# lego.net
KiCad netlist of a schematic drawn in EAGLE
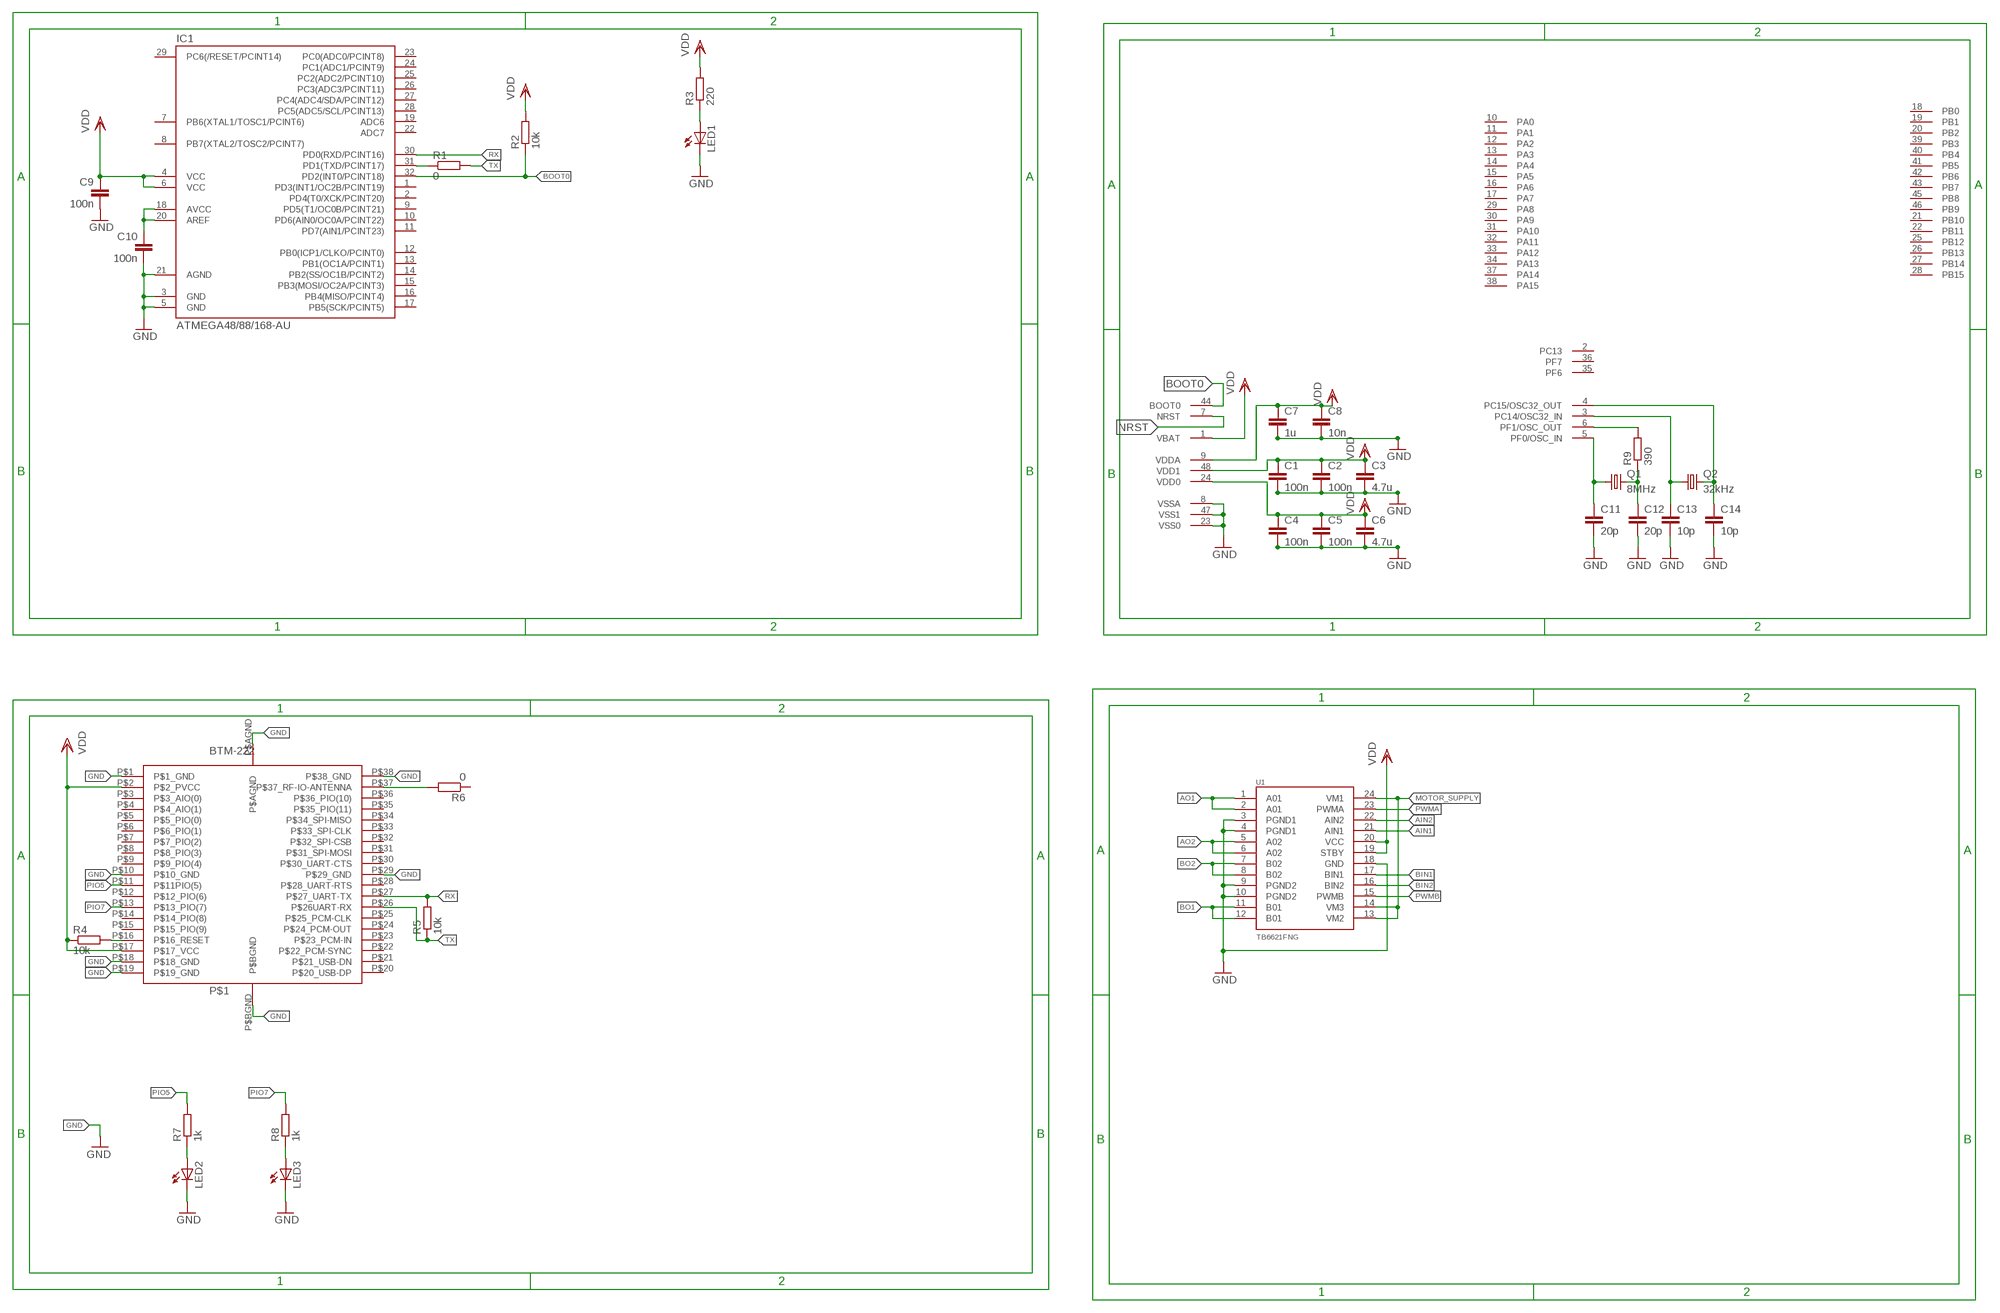
[diagram p0: schematic, sheet 1]

(export (version "E")
  (design (tool "Eeschema 10.0.6"))
  (components
    (comp (ref "C1")
      (value "100n")
      (footprint "eagle-import:C0805")
      (libsource (lib "eagle-import") (part "C-EUC0805"))
    )
    (comp (ref "C2")
      (value "100n")
      (footprint "eagle-import:C0805")
      (libsource (lib "eagle-import") (part "C-EUC0805"))
    )
    (comp (ref "C3")
      (value "4.7u")
      (footprint "eagle-import:C0805")
      (libsource (lib "eagle-import") (part "C-EUC0805"))
    )
    (comp (ref "C4")
      (value "100n")
      (footprint "eagle-import:C0805")
      (libsource (lib "eagle-import") (part "C-EUC0805"))
    )
    (comp (ref "C5")
      (value "100n")
      (footprint "eagle-import:C0805")
      (libsource (lib "eagle-import") (part "C-EUC0805"))
    )
    (comp (ref "C6")
      (value "4.7u")
      (footprint "eagle-import:C0805")
      (libsource (lib "eagle-import") (part "C-EUC0805"))
    )
    (comp (ref "C7")
      (value "1u")
      (footprint "eagle-import:C0805")
      (libsource (lib "eagle-import") (part "C-EUC0805"))
    )
    (comp (ref "C8")
      (value "10n")
      (footprint "eagle-import:C0805")
      (libsource (lib "eagle-import") (part "C-EUC0805"))
    )
    (comp (ref "C9")
      (value "100n")
      (footprint "eagle-import:C0805")
      (libsource (lib "eagle-import") (part "C-EUC0805"))
    )
    (comp (ref "C10")
      (value "100n")
      (footprint "eagle-import:C0805")
      (libsource (lib "eagle-import") (part "C-EUC0805"))
    )
    (comp (ref "C11")
      (value "20p")
      (footprint "eagle-import:C0805")
      (libsource (lib "eagle-import") (part "C-EUC0805"))
    )
    (comp (ref "C12")
      (value "20p")
      (footprint "eagle-import:C0805")
      (libsource (lib "eagle-import") (part "C-EUC0805"))
    )
    (comp (ref "C13")
      (value "10p")
      (footprint "eagle-import:C0805")
      (libsource (lib "eagle-import") (part "C-EUC0805"))
    )
    (comp (ref "C14")
      (value "10p")
      (footprint "eagle-import:C0805")
      (libsource (lib "eagle-import") (part "C-EUC0805"))
    )
    (comp (ref "IC1")
      (value "ATMEGA48/88/168-AU")
      (footprint "eagle-import:TQFP32-08")
      (libsource (lib "eagle-import") (part "ATMEGA48/88/168-AU"))
    )
    (comp (ref "LED1")
      (value "LEDSMT1206")
      (footprint "eagle-import:1206")
      (libsource (lib "eagle-import") (part "LEDSMT1206"))
    )
    (comp (ref "LED2")
      (value "LEDSMT1206")
      (footprint "eagle-import:1206")
      (libsource (lib "eagle-import") (part "LEDSMT1206"))
    )
    (comp (ref "LED3")
      (value "LEDSMT1206")
      (footprint "eagle-import:1206")
      (libsource (lib "eagle-import") (part "LEDSMT1206"))
    )
    (comp (ref "P$1")
      (value "BTM-222")
      (footprint "eagle-import:BTM-222")
      (libsource (lib "eagle-import") (part "BTM-222"))
    )
    (comp (ref "Q1")
      (value "8MHz")
      (footprint "eagle-import:HC49UP")
      (libsource (lib "eagle-import") (part "CRYSTALHC49UP"))
    )
    (comp (ref "Q2")
      (value "32kHz")
      (footprint "eagle-import:HC49UP")
      (libsource (lib "eagle-import") (part "CRYSTALHC49UP"))
    )
    (comp (ref "R1")
      (value "0")
      (footprint "eagle-import:R0805")
      (libsource (lib "eagle-import") (part "R-EU_R0805"))
    )
    (comp (ref "R2")
      (value "10k")
      (footprint "eagle-import:R0805")
      (libsource (lib "eagle-import") (part "R-EU_R0805"))
    )
    (comp (ref "R3")
      (value "220")
      (footprint "eagle-import:R0805")
      (libsource (lib "eagle-import") (part "R-EU_R0805"))
    )
    (comp (ref "R4")
      (value "10k")
      (footprint "eagle-import:R0805")
      (libsource (lib "eagle-import") (part "R-EU_R0805"))
    )
    (comp (ref "R5")
      (value "10k")
      (footprint "eagle-import:R0805")
      (libsource (lib "eagle-import") (part "R-EU_R0805"))
    )
    (comp (ref "R6")
      (value "0")
      (footprint "eagle-import:R0805")
      (libsource (lib "eagle-import") (part "R-EU_R0805"))
    )
    (comp (ref "R7")
      (value "1k")
      (footprint "eagle-import:R0805")
      (libsource (lib "eagle-import") (part "R-EU_R0805"))
    )
    (comp (ref "R8")
      (value "1k")
      (footprint "eagle-import:R0805")
      (libsource (lib "eagle-import") (part "R-EU_R0805"))
    )
    (comp (ref "R9")
      (value "390")
      (footprint "eagle-import:R0805")
      (libsource (lib "eagle-import") (part "R-EU_R0805"))
    )
    (comp (ref "U$1")
      (value "STM32F050")
      (footprint "eagle-import:LQFP48")
      (libsource (lib "eagle-import") (part "STM32F050"))
    )
    (comp (ref "U1")
      (value "TB6621FNG")
      (footprint "eagle-import:SSOP24")
      (libsource (lib "eagle-import") (part "TB6621FNG"))
    )
  )
  (nets
    (net (code "1") (name "AIN1") (class "Default")
      (node (ref "U1") (pin "21") (pinfunction "AIN1_21") (pintype "bidirectional"))
    )
    (net (code "2") (name "AIN2") (class "Default")
      (node (ref "U1") (pin "22") (pinfunction "AIN2_22") (pintype "bidirectional"))
    )
    (net (code "3") (name "AO1") (class "Default")
      (node (ref "U1") (pin "1") (pinfunction "A01_1") (pintype "bidirectional"))
      (node (ref "U1") (pin "2") (pinfunction "A01_2") (pintype "bidirectional"))
    )
    (net (code "4") (name "AO2") (class "Default")
      (node (ref "U1") (pin "5") (pinfunction "A02_5") (pintype "bidirectional"))
      (node (ref "U1") (pin "6") (pinfunction "A02_6") (pintype "bidirectional"))
    )
    (net (code "5") (name "BIN1") (class "Default")
      (node (ref "U1") (pin "17") (pinfunction "BIN1_17") (pintype "bidirectional"))
    )
    (net (code "6") (name "BIN2") (class "Default")
      (node (ref "U1") (pin "16") (pinfunction "BIN2_16") (pintype "bidirectional"))
    )
    (net (code "7") (name "BO1") (class "Default")
      (node (ref "U1") (pin "11") (pinfunction "B01_11") (pintype "bidirectional"))
      (node (ref "U1") (pin "12") (pinfunction "B01_12") (pintype "bidirectional"))
    )
    (net (code "8") (name "BO2") (class "Default")
      (node (ref "U1") (pin "7") (pinfunction "B02_7") (pintype "bidirectional"))
      (node (ref "U1") (pin "8") (pinfunction "B02_8") (pintype "bidirectional"))
    )
    (net (code "9") (name "BOOT0") (class "Default")
      (node (ref "IC1") (pin "32") (pinfunction "PD2(INT0/PCINT18)_32") (pintype "bidirectional"))
      (node (ref "R2") (pin "1") (pinfunction "1_1") (pintype "passive"))
      (node (ref "U$1") (pin "44") (pinfunction "BOOT0_44") (pintype "input"))
    )
    (net (code "10") (name "GND") (class "Default")
      (node (ref "C1") (pin "2") (pinfunction "2_2") (pintype "passive"))
      (node (ref "C10") (pin "2") (pinfunction "2_2") (pintype "passive"))
      (node (ref "C11") (pin "2") (pinfunction "2_2") (pintype "passive"))
      (node (ref "C12") (pin "2") (pinfunction "2_2") (pintype "passive"))
      (node (ref "C13") (pin "2") (pinfunction "2_2") (pintype "passive"))
      (node (ref "C14") (pin "2") (pinfunction "2_2") (pintype "passive"))
      (node (ref "C2") (pin "2") (pinfunction "2_2") (pintype "passive"))
      (node (ref "C3") (pin "2") (pinfunction "2_2") (pintype "passive"))
      (node (ref "C4") (pin "2") (pinfunction "2_2") (pintype "passive"))
      (node (ref "C5") (pin "2") (pinfunction "2_2") (pintype "passive"))
      (node (ref "C6") (pin "2") (pinfunction "2_2") (pintype "passive"))
      (node (ref "C7") (pin "2") (pinfunction "2_2") (pintype "passive"))
      (node (ref "C8") (pin "2") (pinfunction "2_2") (pintype "passive"))
      (node (ref "C9") (pin "2") (pinfunction "2_2") (pintype "passive"))
      (node (ref "IC1") (pin "21") (pinfunction "AGND_21") (pintype "power_in"))
      (node (ref "IC1") (pin "3") (pinfunction "GND_3") (pintype "power_in"))
      (node (ref "IC1") (pin "5") (pinfunction "GND_5") (pintype "power_in"))
      (node (ref "LED1") (pin "C") (pinfunction "C_C") (pintype "passive"))
      (node (ref "LED2") (pin "C") (pinfunction "C_C") (pintype "passive"))
      (node (ref "LED3") (pin "C") (pinfunction "C_C") (pintype "passive"))
      (node (ref "P$1") (pin "P$1") (pinfunction "P$1_GND_P$1") (pintype "power_in"))
      (node (ref "P$1") (pin "P$10") (pinfunction "P$10_GND_P$10") (pintype "power_in"))
      (node (ref "P$1") (pin "P$18") (pinfunction "P$18_GND_P$18") (pintype "power_in"))
      (node (ref "P$1") (pin "P$19") (pinfunction "P$19_GND_P$19") (pintype "power_in"))
      (node (ref "P$1") (pin "P$29") (pinfunction "P$29_GND_P$29") (pintype "power_in"))
      (node (ref "P$1") (pin "P$38") (pinfunction "P$38_GND_P$38") (pintype "power_in"))
      (node (ref "P$1") (pin "P$AGND") (pinfunction "P$AGND_P$AGND") (pintype "power_in"))
      (node (ref "P$1") (pin "P$BGND") (pinfunction "P$BGND_P$BGND") (pintype "power_in"))
      (node (ref "U$1") (pin "23") (pinfunction "VSS0_23") (pintype "power_in"))
      (node (ref "U$1") (pin "47") (pinfunction "VSS1_47") (pintype "power_in"))
      (node (ref "U$1") (pin "8") (pinfunction "VSSA_8") (pintype "power_in"))
      (node (ref "U1") (pin "10") (pinfunction "PGND2_10") (pintype "bidirectional"))
      (node (ref "U1") (pin "18") (pinfunction "GND_18") (pintype "bidirectional"))
      (node (ref "U1") (pin "3") (pinfunction "PGND1_3") (pintype "bidirectional"))
      (node (ref "U1") (pin "4") (pinfunction "PGND1_4") (pintype "bidirectional"))
      (node (ref "U1") (pin "9") (pinfunction "PGND2_9") (pintype "bidirectional"))
    )
    (net (code "11") (name "MOTOR_SUPPLY") (class "Default")
      (node (ref "U1") (pin "13") (pinfunction "VM2_13") (pintype "bidirectional"))
      (node (ref "U1") (pin "14") (pinfunction "VM3_14") (pintype "bidirectional"))
      (node (ref "U1") (pin "24") (pinfunction "VM1_24") (pintype "bidirectional"))
    )
    (net (code "12") (name "NRST") (class "Default")
      (node (ref "U$1") (pin "7") (pinfunction "NRST_7") (pintype "input"))
    )
    (net (code "13") (name "Net-(C12-Pad1)") (class "Default")
      (node (ref "C12") (pin "1") (pinfunction "1_1") (pintype "passive"))
      (node (ref "Q1") (pin "2") (pinfunction "2_2") (pintype "passive"))
      (node (ref "R9") (pin "1") (pinfunction "1_1") (pintype "passive"))
    )
    (net (code "14") (name "Net-(IC1-AREF)") (class "Default")
      (node (ref "C10") (pin "1") (pinfunction "1_1") (pintype "passive"))
      (node (ref "IC1") (pin "18") (pinfunction "AVCC_18") (pintype "passive"))
      (node (ref "IC1") (pin "20") (pinfunction "AREF_20") (pintype "passive"))
    )
    (net (code "15") (name "Net-(IC1-PD1(TXD{slash}PCINT17))") (class "Default")
      (node (ref "IC1") (pin "31") (pinfunction "PD1(TXD/PCINT17)_31") (pintype "bidirectional"))
      (node (ref "R1") (pin "1") (pinfunction "1_1") (pintype "passive"))
    )
    (net (code "16") (name "Net-(LED1-PadA)") (class "Default")
      (node (ref "LED1") (pin "A") (pinfunction "A_A") (pintype "passive"))
      (node (ref "R3") (pin "1") (pinfunction "1_1") (pintype "passive"))
    )
    (net (code "17") (name "Net-(LED2-PadA)") (class "Default")
      (node (ref "LED2") (pin "A") (pinfunction "A_A") (pintype "passive"))
      (node (ref "R7") (pin "1") (pinfunction "1_1") (pintype "passive"))
    )
    (net (code "18") (name "Net-(LED3-PadA)") (class "Default")
      (node (ref "LED3") (pin "A") (pinfunction "A_A") (pintype "passive"))
      (node (ref "R8") (pin "1") (pinfunction "1_1") (pintype "passive"))
    )
    (net (code "19") (name "Net-(P$1-P$16_RESET)") (class "Default")
      (node (ref "P$1") (pin "P$16") (pinfunction "P$16_RESET_P$16") (pintype "input"))
      (node (ref "R4") (pin "2") (pinfunction "2_2") (pintype "passive"))
    )
    (net (code "20") (name "Net-(P$1-P$37_RF-IO-ANTENNA)") (class "Default")
      (node (ref "P$1") (pin "P$37") (pinfunction "P$37_RF-IO-ANTENNA_P$37") (pintype "bidirectional"))
      (node (ref "R6") (pin "2") (pinfunction "2_2") (pintype "passive"))
    )
    (net (code "21") (name "Net-(U$1D-PC14{slash}OSC32_IN)") (class "Default")
      (node (ref "C13") (pin "1") (pinfunction "1_1") (pintype "passive"))
      (node (ref "Q2") (pin "1") (pinfunction "1_1") (pintype "passive"))
      (node (ref "U$1") (pin "3") (pinfunction "PC14/OSC32_IN_3") (pintype "open_collector"))
    )
    (net (code "22") (name "Net-(U$1D-PC15{slash}OSC32_OUT)") (class "Default")
      (node (ref "C14") (pin "1") (pinfunction "1_1") (pintype "passive"))
      (node (ref "Q2") (pin "2") (pinfunction "2_2") (pintype "passive"))
      (node (ref "U$1") (pin "4") (pinfunction "PC15/OSC32_OUT_4") (pintype "open_collector"))
    )
    (net (code "23") (name "Net-(U$1D-PF0{slash}OSC_IN)") (class "Default")
      (node (ref "C11") (pin "1") (pinfunction "1_1") (pintype "passive"))
      (node (ref "Q1") (pin "1") (pinfunction "1_1") (pintype "passive"))
      (node (ref "U$1") (pin "5") (pinfunction "PF0/OSC_IN_5") (pintype "open_collector"))
    )
    (net (code "24") (name "Net-(U$1D-PF1{slash}OSC_OUT)") (class "Default")
      (node (ref "R9") (pin "2") (pinfunction "2_2") (pintype "passive"))
      (node (ref "U$1") (pin "6") (pinfunction "PF1/OSC_OUT_6") (pintype "open_collector"))
    )
    (net (code "25") (name "PIO5") (class "Default")
      (node (ref "P$1") (pin "P$11") (pinfunction "P$11PIO(5)_P$11") (pintype "bidirectional"))
      (node (ref "R7") (pin "2") (pinfunction "2_2") (pintype "passive"))
    )
    (net (code "26") (name "PIO7") (class "Default")
      (node (ref "P$1") (pin "P$13") (pinfunction "P$13_PIO(7)_P$13") (pintype "bidirectional"))
      (node (ref "R8") (pin "2") (pinfunction "2_2") (pintype "passive"))
    )
    (net (code "27") (name "PWMA") (class "Default")
      (node (ref "U1") (pin "23") (pinfunction "PWMA_23") (pintype "bidirectional"))
    )
    (net (code "28") (name "PWMB") (class "Default")
      (node (ref "U1") (pin "15") (pinfunction "PWMB_15") (pintype "bidirectional"))
    )
    (net (code "29") (name "RX") (class "Default")
      (node (ref "IC1") (pin "30") (pinfunction "PD0(RXD/PCINT16)_30") (pintype "bidirectional"))
      (node (ref "P$1") (pin "P$27") (pinfunction "P$27_UART-TX_P$27") (pintype "output"))
      (node (ref "R5") (pin "2") (pinfunction "2_2") (pintype "passive"))
    )
    (net (code "30") (name "TX") (class "Default")
      (node (ref "P$1") (pin "P$26") (pinfunction "P$26UART-RX_P$26") (pintype "input"))
      (node (ref "R1") (pin "2") (pinfunction "2_2") (pintype "passive"))
      (node (ref "R5") (pin "1") (pinfunction "1_1") (pintype "passive"))
    )
    (net (code "31") (name "VDD") (class "Default")
      (node (ref "C1") (pin "1") (pinfunction "1_1") (pintype "passive"))
      (node (ref "C2") (pin "1") (pinfunction "1_1") (pintype "passive"))
      (node (ref "C3") (pin "1") (pinfunction "1_1") (pintype "passive"))
      (node (ref "C4") (pin "1") (pinfunction "1_1") (pintype "passive"))
      (node (ref "C5") (pin "1") (pinfunction "1_1") (pintype "passive"))
      (node (ref "C6") (pin "1") (pinfunction "1_1") (pintype "passive"))
      (node (ref "C7") (pin "1") (pinfunction "1_1") (pintype "passive"))
      (node (ref "C8") (pin "1") (pinfunction "1_1") (pintype "passive"))
      (node (ref "C9") (pin "1") (pinfunction "1_1") (pintype "passive"))
      (node (ref "IC1") (pin "4") (pinfunction "VCC_4") (pintype "power_in"))
      (node (ref "IC1") (pin "6") (pinfunction "VCC_6") (pintype "power_in"))
      (node (ref "P$1") (pin "P$17") (pinfunction "P$17_VCC_P$17") (pintype "power_in"))
      (node (ref "P$1") (pin "P$2") (pinfunction "P$2_PVCC_P$2") (pintype "power_in"))
      (node (ref "R2") (pin "2") (pinfunction "2_2") (pintype "passive"))
      (node (ref "R3") (pin "2") (pinfunction "2_2") (pintype "passive"))
      (node (ref "R4") (pin "1") (pinfunction "1_1") (pintype "passive"))
      (node (ref "U$1") (pin "1") (pinfunction "VBAT_1") (pintype "power_in"))
      (node (ref "U$1") (pin "24") (pinfunction "VDD0_24") (pintype "power_in"))
      (node (ref "U$1") (pin "48") (pinfunction "VDD1_48") (pintype "power_in"))
      (node (ref "U$1") (pin "9") (pinfunction "VDDA_9") (pintype "power_in"))
      (node (ref "U1") (pin "19") (pinfunction "STBY_19") (pintype "bidirectional"))
      (node (ref "U1") (pin "20") (pinfunction "VCC_20") (pintype "bidirectional"))
    )
    (net (code "32") (name "unconnected-(IC1-ADC6-Pad19)") (class "Default")
      (node (ref "IC1") (pin "19") (pinfunction "ADC6_19") (pintype "passive"))
    )
    (net (code "33") (name "unconnected-(IC1-ADC7-Pad22)") (class "Default")
      (node (ref "IC1") (pin "22") (pinfunction "ADC7_22") (pintype "passive"))
    )
    (net (code "34") (name "unconnected-(IC1-PB0(ICP1{slash}CLKO{slash}PCINT0)-Pad12)") (class "Default")
      (node (ref "IC1") (pin "12") (pinfunction "PB0(ICP1/CLKO/PCINT0)_12") (pintype "bidirectional"))
    )
    (net (code "35") (name "unconnected-(IC1-PB1(OC1A{slash}PCINT1)-Pad13)") (class "Default")
      (node (ref "IC1") (pin "13") (pinfunction "PB1(OC1A/PCINT1)_13") (pintype "bidirectional"))
    )
    (net (code "36") (name "unconnected-(IC1-PB2(SS{slash}OC1B{slash}PCINT2)-Pad14)") (class "Default")
      (node (ref "IC1") (pin "14") (pinfunction "PB2(SS/OC1B/PCINT2)_14") (pintype "bidirectional"))
    )
    (net (code "37") (name "unconnected-(IC1-PB3(MOSI{slash}OC2A{slash}PCINT3)-Pad15)") (class "Default")
      (node (ref "IC1") (pin "15") (pinfunction "PB3(MOSI/OC2A/PCINT3)_15") (pintype "bidirectional"))
    )
    (net (code "38") (name "unconnected-(IC1-PB4(MISO{slash}PCINT4)-Pad16)") (class "Default")
      (node (ref "IC1") (pin "16") (pinfunction "PB4(MISO/PCINT4)_16") (pintype "bidirectional"))
    )
    (net (code "39") (name "unconnected-(IC1-PB5(SCK{slash}PCINT5)-Pad17)") (class "Default")
      (node (ref "IC1") (pin "17") (pinfunction "PB5(SCK/PCINT5)_17") (pintype "bidirectional"))
    )
    (net (code "40") (name "unconnected-(IC1-PB6(XTAL1{slash}TOSC1{slash}PCINT6)-Pad7)") (class "Default")
      (node (ref "IC1") (pin "7") (pinfunction "PB6(XTAL1/TOSC1/PCINT6)_7") (pintype "bidirectional"))
    )
    (net (code "41") (name "unconnected-(IC1-PB7(XTAL2{slash}TOSC2{slash}PCINT7)-Pad8)") (class "Default")
      (node (ref "IC1") (pin "8") (pinfunction "PB7(XTAL2/TOSC2/PCINT7)_8") (pintype "bidirectional"))
    )
    (net (code "42") (name "unconnected-(IC1-PC0(ADC0{slash}PCINT8)-Pad23)") (class "Default")
      (node (ref "IC1") (pin "23") (pinfunction "PC0(ADC0/PCINT8)_23") (pintype "bidirectional"))
    )
    (net (code "43") (name "unconnected-(IC1-PC1(ADC1{slash}PCINT9)-Pad24)") (class "Default")
      (node (ref "IC1") (pin "24") (pinfunction "PC1(ADC1/PCINT9)_24") (pintype "bidirectional"))
    )
    (net (code "44") (name "unconnected-(IC1-PC2(ADC2{slash}PCINT10)-Pad25)") (class "Default")
      (node (ref "IC1") (pin "25") (pinfunction "PC2(ADC2/PCINT10)_25") (pintype "bidirectional"))
    )
    (net (code "45") (name "unconnected-(IC1-PC3(ADC3{slash}PCINT11)-Pad26)") (class "Default")
      (node (ref "IC1") (pin "26") (pinfunction "PC3(ADC3/PCINT11)_26") (pintype "bidirectional"))
    )
    (net (code "46") (name "unconnected-(IC1-PC4(ADC4{slash}SDA{slash}PCINT12)-Pad27)") (class "Default")
      (node (ref "IC1") (pin "27") (pinfunction "PC4(ADC4/SDA/PCINT12)_27") (pintype "bidirectional"))
    )
    (net (code "47") (name "unconnected-(IC1-PC5(ADC5{slash}SCL{slash}PCINT13)-Pad28)") (class "Default")
      (node (ref "IC1") (pin "28") (pinfunction "PC5(ADC5/SCL/PCINT13)_28") (pintype "bidirectional"))
    )
    (net (code "48") (name "unconnected-(IC1-PC6({slash}RESET{slash}PCINT14)-Pad29)") (class "Default")
      (node (ref "IC1") (pin "29") (pinfunction "PC6(/RESET/PCINT14)_29") (pintype "bidirectional"))
    )
    (net (code "49") (name "unconnected-(IC1-PD3(INT1{slash}OC2B{slash}PCINT19)-Pad1)") (class "Default")
      (node (ref "IC1") (pin "1") (pinfunction "PD3(INT1/OC2B/PCINT19)_1") (pintype "bidirectional"))
    )
    (net (code "50") (name "unconnected-(IC1-PD4(T0{slash}XCK{slash}PCINT20)-Pad2)") (class "Default")
      (node (ref "IC1") (pin "2") (pinfunction "PD4(T0/XCK/PCINT20)_2") (pintype "bidirectional"))
    )
    (net (code "51") (name "unconnected-(IC1-PD5(T1{slash}OC0B{slash}PCINT21)-Pad9)") (class "Default")
      (node (ref "IC1") (pin "9") (pinfunction "PD5(T1/OC0B/PCINT21)_9") (pintype "bidirectional"))
    )
    (net (code "52") (name "unconnected-(IC1-PD6(AIN0{slash}OC0A{slash}PCINT22)-Pad10)") (class "Default")
      (node (ref "IC1") (pin "10") (pinfunction "PD6(AIN0/OC0A/PCINT22)_10") (pintype "bidirectional"))
    )
    (net (code "53") (name "unconnected-(IC1-PD7(AIN1{slash}PCINT23)-Pad11)") (class "Default")
      (node (ref "IC1") (pin "11") (pinfunction "PD7(AIN1/PCINT23)_11") (pintype "bidirectional"))
    )
    (net (code "54") (name "unconnected-(P$1-P$3_AIO(0)-PadP$3)") (class "Default")
      (node (ref "P$1") (pin "P$3") (pinfunction "P$3_AIO(0)_P$3") (pintype "bidirectional"))
    )
    (net (code "55") (name "unconnected-(P$1-P$4_AIO(1)-PadP$4)") (class "Default")
      (node (ref "P$1") (pin "P$4") (pinfunction "P$4_AIO(1)_P$4") (pintype "bidirectional"))
    )
    (net (code "56") (name "unconnected-(P$1-P$5_PIO(0)-PadP$5)") (class "Default")
      (node (ref "P$1") (pin "P$5") (pinfunction "P$5_PIO(0)_P$5") (pintype "bidirectional"))
    )
    (net (code "57") (name "unconnected-(P$1-P$6_PIO(1)-PadP$6)") (class "Default")
      (node (ref "P$1") (pin "P$6") (pinfunction "P$6_PIO(1)_P$6") (pintype "bidirectional"))
    )
    (net (code "58") (name "unconnected-(P$1-P$7_PIO(2)-PadP$7)") (class "Default")
      (node (ref "P$1") (pin "P$7") (pinfunction "P$7_PIO(2)_P$7") (pintype "bidirectional"))
    )
    (net (code "59") (name "unconnected-(P$1-P$8_PIO(3)-PadP$8)") (class "Default")
      (node (ref "P$1") (pin "P$8") (pinfunction "P$8_PIO(3)_P$8") (pintype "bidirectional"))
    )
    (net (code "60") (name "unconnected-(P$1-P$9_PIO(4)-PadP$9)") (class "Default")
      (node (ref "P$1") (pin "P$9") (pinfunction "P$9_PIO(4)_P$9") (pintype "bidirectional"))
    )
    (net (code "61") (name "unconnected-(P$1-P$12_PIO(6)-PadP$12)") (class "Default")
      (node (ref "P$1") (pin "P$12") (pinfunction "P$12_PIO(6)_P$12") (pintype "bidirectional"))
    )
    (net (code "62") (name "unconnected-(P$1-P$14_PIO(8)-PadP$14)") (class "Default")
      (node (ref "P$1") (pin "P$14") (pinfunction "P$14_PIO(8)_P$14") (pintype "bidirectional"))
    )
    (net (code "63") (name "unconnected-(P$1-P$15_PIO(9)-PadP$15)") (class "Default")
      (node (ref "P$1") (pin "P$15") (pinfunction "P$15_PIO(9)_P$15") (pintype "bidirectional"))
    )
    (net (code "64") (name "unconnected-(P$1-P$20_USB-DP-PadP$20)") (class "Default")
      (node (ref "P$1") (pin "P$20") (pinfunction "P$20_USB-DP_P$20") (pintype "bidirectional"))
    )
    (net (code "65") (name "unconnected-(P$1-P$21_USB-DN-PadP$21)") (class "Default")
      (node (ref "P$1") (pin "P$21") (pinfunction "P$21_USB-DN_P$21") (pintype "bidirectional"))
    )
    (net (code "66") (name "unconnected-(P$1-P$22_PCM-SYNC-PadP$22)") (class "Default")
      (node (ref "P$1") (pin "P$22") (pinfunction "P$22_PCM-SYNC_P$22") (pintype "bidirectional"))
    )
    (net (code "67") (name "unconnected-(P$1-P$23_PCM-IN-PadP$23)") (class "Default")
      (node (ref "P$1") (pin "P$23") (pinfunction "P$23_PCM-IN_P$23") (pintype "input"))
    )
    (net (code "68") (name "unconnected-(P$1-P$24_PCM-OUT-PadP$24)") (class "Default")
      (node (ref "P$1") (pin "P$24") (pinfunction "P$24_PCM-OUT_P$24") (pintype "output"))
    )
    (net (code "69") (name "unconnected-(P$1-P$25_PCM-CLK-PadP$25)") (class "Default")
      (node (ref "P$1") (pin "P$25") (pinfunction "P$25_PCM-CLK_P$25") (pintype "bidirectional"))
    )
    (net (code "70") (name "unconnected-(P$1-P$28_UART-RTS-PadP$28)") (class "Default")
      (node (ref "P$1") (pin "P$28") (pinfunction "P$28_UART-RTS_P$28") (pintype "output"))
    )
    (net (code "71") (name "unconnected-(P$1-P$30_UART-CTS-PadP$30)") (class "Default")
      (node (ref "P$1") (pin "P$30") (pinfunction "P$30_UART-CTS_P$30") (pintype "input"))
    )
    (net (code "72") (name "unconnected-(P$1-P$31_SPI-MOSI-PadP$31)") (class "Default")
      (node (ref "P$1") (pin "P$31") (pinfunction "P$31_SPI-MOSI_P$31") (pintype "input"))
    )
    (net (code "73") (name "unconnected-(P$1-P$32_SPI-CSB-PadP$32)") (class "Default")
      (node (ref "P$1") (pin "P$32") (pinfunction "P$32_SPI-CSB_P$32") (pintype "input"))
    )
    (net (code "74") (name "unconnected-(P$1-P$33_SPI-CLK-PadP$33)") (class "Default")
      (node (ref "P$1") (pin "P$33") (pinfunction "P$33_SPI-CLK_P$33") (pintype "input"))
    )
    (net (code "75") (name "unconnected-(P$1-P$34_SPI-MISO-PadP$34)") (class "Default")
      (node (ref "P$1") (pin "P$34") (pinfunction "P$34_SPI-MISO_P$34") (pintype "output"))
    )
    (net (code "76") (name "unconnected-(P$1-P$35_PIO(11)-PadP$35)") (class "Default")
      (node (ref "P$1") (pin "P$35") (pinfunction "P$35_PIO(11)_P$35") (pintype "bidirectional"))
    )
    (net (code "77") (name "unconnected-(P$1-P$36_PIO(10)-PadP$36)") (class "Default")
      (node (ref "P$1") (pin "P$36") (pinfunction "P$36_PIO(10)_P$36") (pintype "bidirectional"))
    )
    (net (code "78") (name "unconnected-(R6-Pad1)") (class "Default")
      (node (ref "R6") (pin "1") (pinfunction "1_1") (pintype "passive"))
    )
    (net (code "79") (name "unconnected-(U$1A-PA0-Pad10)") (class "Default")
      (node (ref "U$1") (pin "10") (pinfunction "PA0_10") (pintype "open_collector"))
    )
    (net (code "80") (name "unconnected-(U$1A-PA1-Pad11)") (class "Default")
      (node (ref "U$1") (pin "11") (pinfunction "PA1_11") (pintype "open_collector"))
    )
    (net (code "81") (name "unconnected-(U$1A-PA2-Pad12)") (class "Default")
      (node (ref "U$1") (pin "12") (pinfunction "PA2_12") (pintype "open_collector"))
    )
    (net (code "82") (name "unconnected-(U$1A-PA3-Pad13)") (class "Default")
      (node (ref "U$1") (pin "13") (pinfunction "PA3_13") (pintype "open_collector"))
    )
    (net (code "83") (name "unconnected-(U$1A-PA4-Pad14)") (class "Default")
      (node (ref "U$1") (pin "14") (pinfunction "PA4_14") (pintype "open_collector"))
    )
    (net (code "84") (name "unconnected-(U$1A-PA5-Pad15)") (class "Default")
      (node (ref "U$1") (pin "15") (pinfunction "PA5_15") (pintype "open_collector"))
    )
    (net (code "85") (name "unconnected-(U$1A-PA6-Pad16)") (class "Default")
      (node (ref "U$1") (pin "16") (pinfunction "PA6_16") (pintype "open_collector"))
    )
    (net (code "86") (name "unconnected-(U$1A-PA7-Pad17)") (class "Default")
      (node (ref "U$1") (pin "17") (pinfunction "PA7_17") (pintype "open_collector"))
    )
    (net (code "87") (name "unconnected-(U$1A-PA8-Pad29)") (class "Default")
      (node (ref "U$1") (pin "29") (pinfunction "PA8_29") (pintype "open_collector"))
    )
    (net (code "88") (name "unconnected-(U$1A-PA9-Pad30)") (class "Default")
      (node (ref "U$1") (pin "30") (pinfunction "PA9_30") (pintype "open_collector"))
    )
    (net (code "89") (name "unconnected-(U$1A-PA10-Pad31)") (class "Default")
      (node (ref "U$1") (pin "31") (pinfunction "PA10_31") (pintype "open_collector"))
    )
    (net (code "90") (name "unconnected-(U$1A-PA11-Pad32)") (class "Default")
      (node (ref "U$1") (pin "32") (pinfunction "PA11_32") (pintype "open_collector"))
    )
    (net (code "91") (name "unconnected-(U$1A-PA12-Pad33)") (class "Default")
      (node (ref "U$1") (pin "33") (pinfunction "PA12_33") (pintype "open_collector"))
    )
    (net (code "92") (name "unconnected-(U$1A-PA13-Pad34)") (class "Default")
      (node (ref "U$1") (pin "34") (pinfunction "PA13_34") (pintype "open_collector"))
    )
    (net (code "93") (name "unconnected-(U$1A-PA14-Pad37)") (class "Default")
      (node (ref "U$1") (pin "37") (pinfunction "PA14_37") (pintype "open_collector"))
    )
    (net (code "94") (name "unconnected-(U$1A-PA15-Pad38)") (class "Default")
      (node (ref "U$1") (pin "38") (pinfunction "PA15_38") (pintype "open_collector"))
    )
    (net (code "95") (name "unconnected-(U$1B-PB0-Pad18)") (class "Default")
      (node (ref "U$1") (pin "18") (pinfunction "PB0_18") (pintype "open_collector"))
    )
    (net (code "96") (name "unconnected-(U$1B-PB1-Pad19)") (class "Default")
      (node (ref "U$1") (pin "19") (pinfunction "PB1_19") (pintype "open_collector"))
    )
    (net (code "97") (name "unconnected-(U$1B-PB2-Pad20)") (class "Default")
      (node (ref "U$1") (pin "20") (pinfunction "PB2_20") (pintype "open_collector"))
    )
    (net (code "98") (name "unconnected-(U$1B-PB3-Pad39)") (class "Default")
      (node (ref "U$1") (pin "39") (pinfunction "PB3_39") (pintype "open_collector"))
    )
    (net (code "99") (name "unconnected-(U$1B-PB4-Pad40)") (class "Default")
      (node (ref "U$1") (pin "40") (pinfunction "PB4_40") (pintype "open_collector"))
    )
    (net (code "100") (name "unconnected-(U$1B-PB5-Pad41)") (class "Default")
      (node (ref "U$1") (pin "41") (pinfunction "PB5_41") (pintype "open_collector"))
    )
    (net (code "101") (name "unconnected-(U$1B-PB6-Pad42)") (class "Default")
      (node (ref "U$1") (pin "42") (pinfunction "PB6_42") (pintype "open_collector"))
    )
    (net (code "102") (name "unconnected-(U$1B-PB7-Pad43)") (class "Default")
      (node (ref "U$1") (pin "43") (pinfunction "PB7_43") (pintype "open_collector"))
    )
    (net (code "103") (name "unconnected-(U$1B-PB8-Pad45)") (class "Default")
      (node (ref "U$1") (pin "45") (pinfunction "PB8_45") (pintype "open_collector"))
    )
    (net (code "104") (name "unconnected-(U$1B-PB9-Pad46)") (class "Default")
      (node (ref "U$1") (pin "46") (pinfunction "PB9_46") (pintype "open_collector"))
    )
    (net (code "105") (name "unconnected-(U$1B-PB10-Pad21)") (class "Default")
      (node (ref "U$1") (pin "21") (pinfunction "PB10_21") (pintype "open_collector"))
    )
    (net (code "106") (name "unconnected-(U$1B-PB11-Pad22)") (class "Default")
      (node (ref "U$1") (pin "22") (pinfunction "PB11_22") (pintype "open_collector"))
    )
    (net (code "107") (name "unconnected-(U$1B-PB12-Pad25)") (class "Default")
      (node (ref "U$1") (pin "25") (pinfunction "PB12_25") (pintype "open_collector"))
    )
    (net (code "108") (name "unconnected-(U$1B-PB13-Pad26)") (class "Default")
      (node (ref "U$1") (pin "26") (pinfunction "PB13_26") (pintype "open_collector"))
    )
    (net (code "109") (name "unconnected-(U$1B-PB14-Pad27)") (class "Default")
      (node (ref "U$1") (pin "27") (pinfunction "PB14_27") (pintype "open_collector"))
    )
    (net (code "110") (name "unconnected-(U$1B-PB15-Pad28)") (class "Default")
      (node (ref "U$1") (pin "28") (pinfunction "PB15_28") (pintype "open_collector"))
    )
    (net (code "111") (name "unconnected-(U$1D-PC13-Pad2)") (class "Default")
      (node (ref "U$1") (pin "2") (pinfunction "PC13_2") (pintype "bidirectional"))
    )
    (net (code "112") (name "unconnected-(U$1D-PF6-Pad35)") (class "Default")
      (node (ref "U$1") (pin "35") (pinfunction "PF6_35") (pintype "bidirectional"))
    )
    (net (code "113") (name "unconnected-(U$1D-PF7-Pad36)") (class "Default")
      (node (ref "U$1") (pin "36") (pinfunction "PF7_36") (pintype "bidirectional"))
    )
  )
)
